# output_controller_schematic.net
KiCad netlist of a schematic drawn in EAGLE
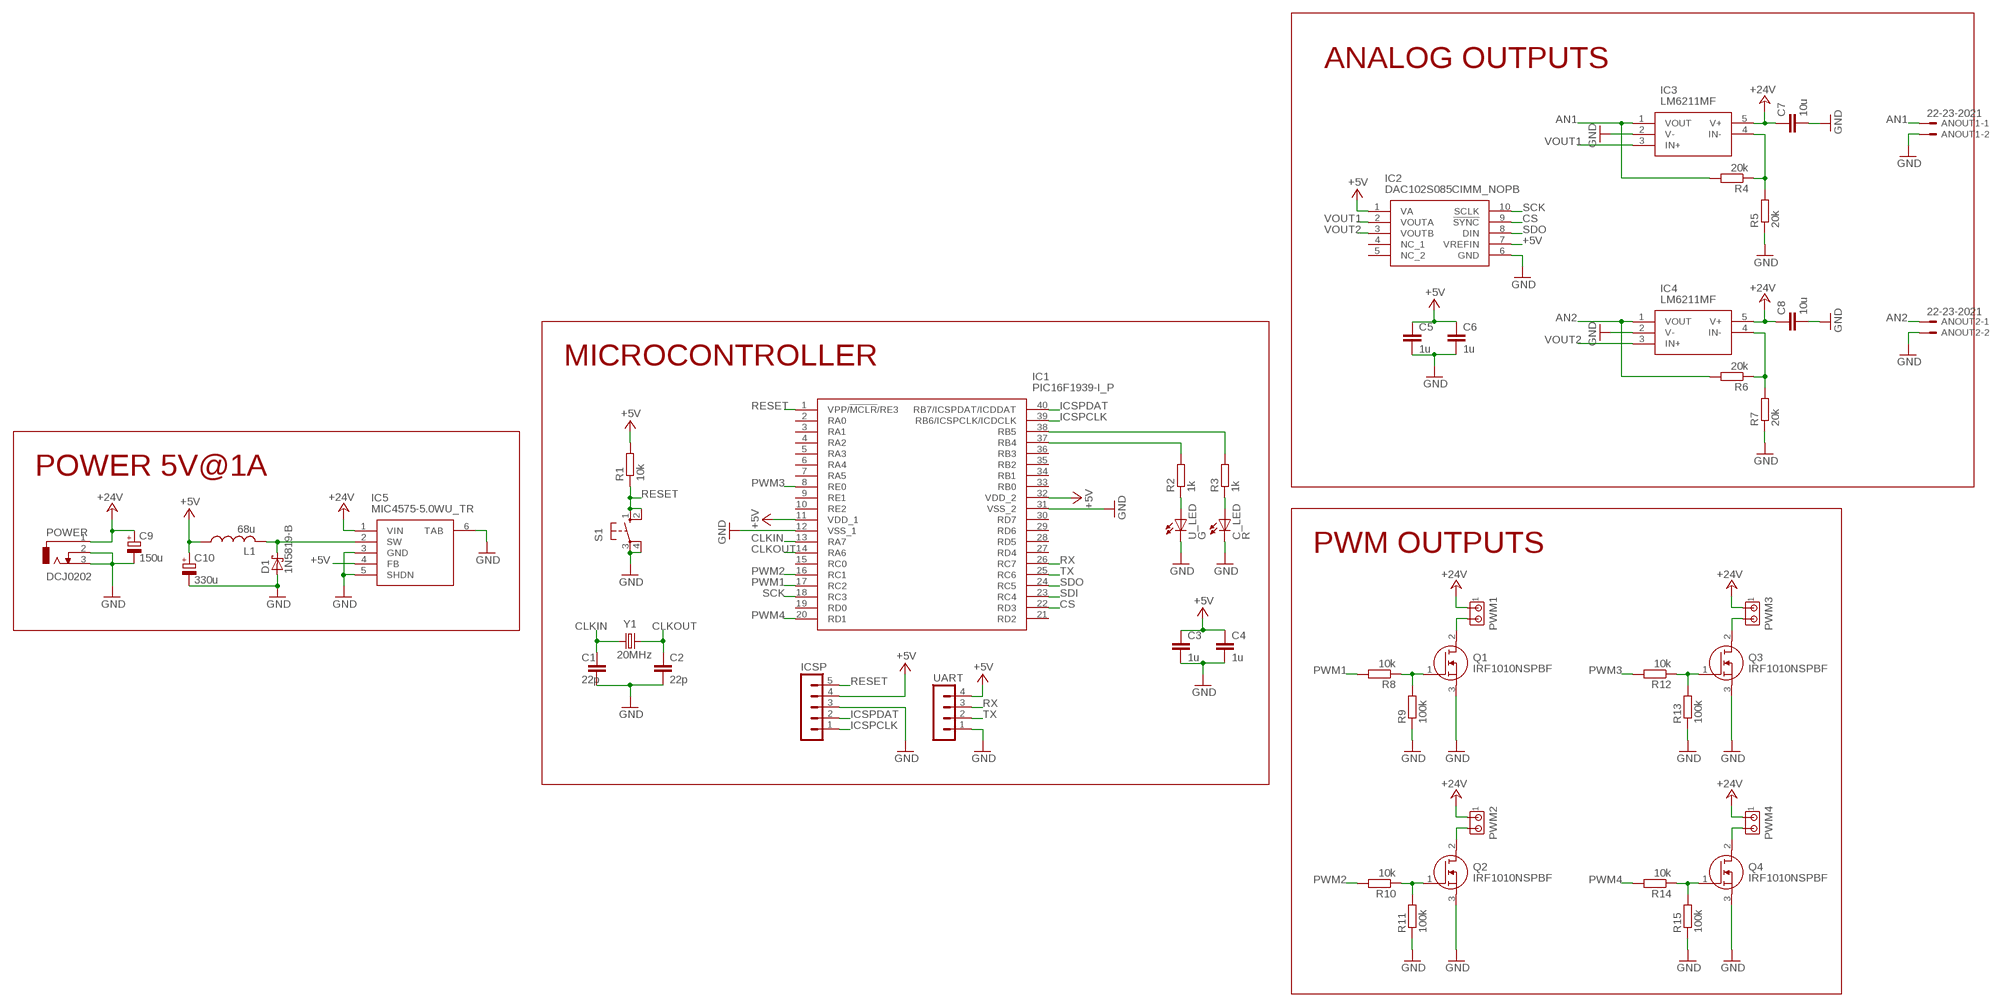
[diagram p0: schematic, sheet 1]

(export (version "E")
  (design (tool "Eeschema 10.0.6"))
  (components
    (comp (ref "ANOUT1")
      (value "22-23-2021")
      (footprint "eagle-import:22-23-2021")
      (fields (field (name "MF") "MOLEX"))
      (libsource (lib "eagle-import") (part "22-23-2021"))
    )
    (comp (ref "ANOUT2")
      (value "22-23-2021")
      (footprint "eagle-import:22-23-2021")
      (fields (field (name "MF") "MOLEX"))
      (libsource (lib "eagle-import") (part "22-23-2021"))
    )
    (comp (ref "C1")
      (value "22p")
      (footprint "eagle-import:C1206")
      (libsource (lib "eagle-import") (part "C-EUC1206"))
    )
    (comp (ref "C2")
      (value "22p")
      (footprint "eagle-import:C1206")
      (libsource (lib "eagle-import") (part "C-EUC1206"))
    )
    (comp (ref "C3")
      (value "1u")
      (footprint "eagle-import:C1206")
      (libsource (lib "eagle-import") (part "C-EUC1206"))
    )
    (comp (ref "C4")
      (value "1u")
      (footprint "eagle-import:C1206")
      (libsource (lib "eagle-import") (part "C-EUC1206"))
    )
    (comp (ref "C5")
      (value "1u")
      (footprint "eagle-import:C1206")
      (libsource (lib "eagle-import") (part "C-EUC1206"))
    )
    (comp (ref "C6")
      (value "1u")
      (footprint "eagle-import:C1206")
      (libsource (lib "eagle-import") (part "C-EUC1206"))
    )
    (comp (ref "C7")
      (value "10u")
      (footprint "eagle-import:C1206")
      (libsource (lib "eagle-import") (part "C-EUC1206"))
    )
    (comp (ref "C8")
      (value "10u")
      (footprint "eagle-import:C1206")
      (libsource (lib "eagle-import") (part "C-EUC1206"))
    )
    (comp (ref "C9")
      (value "150u")
      (footprint "eagle-import:175TMP-0810")
      (libsource (lib "eagle-import") (part "CPOL-EU175TMP-0810"))
    )
    (comp (ref "C10")
      (value "330u")
      (footprint "eagle-import:175TMP-0810")
      (libsource (lib "eagle-import") (part "CPOL-EU175TMP-0810"))
    )
    (comp (ref "C_LED")
      (value "R")
      (footprint "eagle-import:CHIPLED_1206")
      (libsource (lib "eagle-import") (part "LEDCHIPLED_1206"))
    )
    (comp (ref "D1")
      (value "1N5819-B")
      (footprint "eagle-import:DO41-7.6")
      (libsource (lib "eagle-import") (part "1N5819-B"))
    )
    (comp (ref "IC1")
      (value "PIC16F1939-I_P")
      (footprint "eagle-import:DIP1543W58P254L5175H635Q40N")
      (fields
        (field (name "ARROW_PART_NUMBER") "PIC16F1939-I/P")
        (field (name "MOUSER_PART_NUMBER") "579-PIC16F1939-I/P")
      )
      (libsource (lib "eagle-import") (part "PIC16F1939-I_P"))
    )
    (comp (ref "IC2")
      (value "DAC102S085CIMM_NOPB")
      (footprint "eagle-import:SOP50P490X110-10N")
      (fields
        (field (name "ARROW_PART_NUMBER") "DAC102S085CIMM/NOPB")
        (field (name "MOUSER_PART_NUMBER") "926-DA102S085CIMMNPB")
      )
      (libsource (lib "eagle-import") (part "DAC102S085CIMM_NOPB"))
    )
    (comp (ref "IC3")
      (value "LM6211MF")
      (footprint "eagle-import:SOT95P284X122-5N")
      (fields (field (name "MOUSER_PART_NUMBER") "926-LM6211MF"))
      (libsource (lib "eagle-import") (part "LM6211MF"))
    )
    (comp (ref "IC4")
      (value "LM6211MF")
      (footprint "eagle-import:SOT95P284X122-5N")
      (fields (field (name "MOUSER_PART_NUMBER") "926-LM6211MF"))
      (libsource (lib "eagle-import") (part "LM6211MF"))
    )
    (comp (ref "IC5")
      (value "MIC4575-5.0WU_TR")
      (footprint "eagle-import:MIC2930112WU")
      (fields (field (name "ARROW_PART_NUMBER") "MIC4575-5.0WU TR"))
      (libsource (lib "eagle-import") (part "MIC4575-5.0WU_TR"))
    )
    (comp (ref "ICSP")
      (value "MA05-1")
      (footprint "eagle-import:MA05-1")
      (libsource (lib "eagle-import") (part "MA05-1"))
    )
    (comp (ref "L1")
      (value "68u")
      (footprint "eagle-import:L5650M")
      (libsource (lib "eagle-import") (part "L-USL5650M"))
    )
    (comp (ref "POWER")
      (value "DCJ0202")
      (footprint "eagle-import:DCJ0202")
      (libsource (lib "eagle-import") (part "DCJ0202"))
    )
    (comp (ref "PWM1")
      (value "MTA02-156")
      (footprint "eagle-import:1X2MTA")
      (libsource (lib "eagle-import") (part "MTA02-156"))
    )
    (comp (ref "PWM2")
      (value "MTA02-156")
      (footprint "eagle-import:1X2MTA")
      (libsource (lib "eagle-import") (part "MTA02-156"))
    )
    (comp (ref "PWM3")
      (value "MTA02-156")
      (footprint "eagle-import:1X2MTA")
      (libsource (lib "eagle-import") (part "MTA02-156"))
    )
    (comp (ref "PWM4")
      (value "MTA02-156")
      (footprint "eagle-import:1X2MTA")
      (libsource (lib "eagle-import") (part "MTA02-156"))
    )
    (comp (ref "Q1")
      (value "IRF1010NSPBF")
      (footprint "eagle-import:IRF2804STRLPBF")
      (fields (field (name "MOUSER_PART_NUMBER") "942-IRF1010NSPBF"))
      (libsource (lib "eagle-import") (part "IRF1010NSPBF"))
    )
    (comp (ref "Q2")
      (value "IRF1010NSPBF")
      (footprint "eagle-import:IRF2804STRLPBF")
      (fields (field (name "MOUSER_PART_NUMBER") "942-IRF1010NSPBF"))
      (libsource (lib "eagle-import") (part "IRF1010NSPBF"))
    )
    (comp (ref "Q3")
      (value "IRF1010NSPBF")
      (footprint "eagle-import:IRF2804STRLPBF")
      (fields (field (name "MOUSER_PART_NUMBER") "942-IRF1010NSPBF"))
      (libsource (lib "eagle-import") (part "IRF1010NSPBF"))
    )
    (comp (ref "Q4")
      (value "IRF1010NSPBF")
      (footprint "eagle-import:IRF2804STRLPBF")
      (fields (field (name "MOUSER_PART_NUMBER") "942-IRF1010NSPBF"))
      (libsource (lib "eagle-import") (part "IRF1010NSPBF"))
    )
    (comp (ref "R1")
      (value "10k")
      (footprint "eagle-import:R1206")
      (libsource (lib "eagle-import") (part "R-EU_R1206"))
    )
    (comp (ref "R2")
      (value "1k")
      (footprint "eagle-import:R1206")
      (libsource (lib "eagle-import") (part "R-EU_R1206"))
    )
    (comp (ref "R3")
      (value "1k")
      (footprint "eagle-import:R1206")
      (libsource (lib "eagle-import") (part "R-EU_R1206"))
    )
    (comp (ref "R4")
      (value "20k")
      (footprint "eagle-import:R1206")
      (libsource (lib "eagle-import") (part "R-EU_R1206"))
    )
    (comp (ref "R5")
      (value "20k")
      (footprint "eagle-import:R1206")
      (libsource (lib "eagle-import") (part "R-EU_R1206"))
    )
    (comp (ref "R6")
      (value "20k")
      (footprint "eagle-import:R1206")
      (libsource (lib "eagle-import") (part "R-EU_R1206"))
    )
    (comp (ref "R7")
      (value "20k")
      (footprint "eagle-import:R1206")
      (libsource (lib "eagle-import") (part "R-EU_R1206"))
    )
    (comp (ref "R8")
      (value "10k")
      (footprint "eagle-import:R1206")
      (libsource (lib "eagle-import") (part "R-EU_R1206"))
    )
    (comp (ref "R9")
      (value "100k")
      (footprint "eagle-import:R1206")
      (libsource (lib "eagle-import") (part "R-EU_R1206"))
    )
    (comp (ref "R10")
      (value "10k")
      (footprint "eagle-import:R1206")
      (libsource (lib "eagle-import") (part "R-EU_R1206"))
    )
    (comp (ref "R11")
      (value "100k")
      (footprint "eagle-import:R1206")
      (libsource (lib "eagle-import") (part "R-EU_R1206"))
    )
    (comp (ref "R12")
      (value "10k")
      (footprint "eagle-import:R1206")
      (libsource (lib "eagle-import") (part "R-EU_R1206"))
    )
    (comp (ref "R13")
      (value "100k")
      (footprint "eagle-import:R1206")
      (libsource (lib "eagle-import") (part "R-EU_R1206"))
    )
    (comp (ref "R14")
      (value "10k")
      (footprint "eagle-import:R1206")
      (libsource (lib "eagle-import") (part "R-EU_R1206"))
    )
    (comp (ref "R15")
      (value "100k")
      (footprint "eagle-import:R1206")
      (libsource (lib "eagle-import") (part "R-EU_R1206"))
    )
    (comp (ref "S1")
      (value "10-XX")
      (footprint "eagle-import:B3F-10XX")
      (fields (field (name "MPN") "B3F-1000"))
      (libsource (lib "eagle-import") (part "10-XX"))
    )
    (comp (ref "UART")
      (value "MA04-1")
      (footprint "eagle-import:MA04-1")
      (libsource (lib "eagle-import") (part "MA04-1"))
    )
    (comp (ref "U_LED")
      (value "G")
      (footprint "eagle-import:CHIPLED_1206")
      (libsource (lib "eagle-import") (part "LEDCHIPLED_1206"))
    )
    (comp (ref "Y1")
      (value "20MHz")
      (footprint "eagle-import:HC49_S")
      (libsource (lib "eagle-import") (part "CRYSTALHC49S"))
    )
  )
  (nets
    (net (code "1") (name "+5V") (class "Default")
      (node (ref "C10") (pin "+") (pinfunction "+_+") (pintype "passive"))
      (node (ref "C3") (pin "1") (pinfunction "1_1") (pintype "passive"))
      (node (ref "C4") (pin "1") (pinfunction "1_1") (pintype "passive"))
      (node (ref "C5") (pin "1") (pinfunction "1_1") (pintype "passive"))
      (node (ref "C6") (pin "1") (pinfunction "1_1") (pintype "passive"))
      (node (ref "IC1") (pin "11") (pinfunction "VDD_1_11") (pintype "bidirectional"))
      (node (ref "IC1") (pin "32") (pinfunction "VDD_2_32") (pintype "bidirectional"))
      (node (ref "IC2") (pin "1") (pinfunction "VA_1") (pintype "bidirectional"))
      (node (ref "IC2") (pin "7") (pinfunction "VREFIN_7") (pintype "bidirectional"))
      (node (ref "IC5") (pin "4") (pinfunction "FB_4") (pintype "bidirectional"))
      (node (ref "ICSP") (pin "4") (pinfunction "4_4") (pintype "passive"))
      (node (ref "L1") (pin "1") (pinfunction "1_1") (pintype "passive"))
      (node (ref "R1") (pin "2") (pinfunction "2_2") (pintype "passive"))
      (node (ref "UART") (pin "4") (pinfunction "4_4") (pintype "passive"))
    )
    (net (code "2") (name "+24V") (class "Default")
      (node (ref "C7") (pin "1") (pinfunction "1_1") (pintype "passive"))
      (node (ref "C8") (pin "1") (pinfunction "1_1") (pintype "passive"))
      (node (ref "C9") (pin "+") (pinfunction "+_+") (pintype "passive"))
      (node (ref "IC3") (pin "5") (pinfunction "V+_5") (pintype "bidirectional"))
      (node (ref "IC4") (pin "5") (pinfunction "V+_5") (pintype "bidirectional"))
      (node (ref "IC5") (pin "1") (pinfunction "VIN_1") (pintype "bidirectional"))
      (node (ref "POWER") (pin "1") (pinfunction "1_1") (pintype "passive"))
      (node (ref "PWM1") (pin "1") (pinfunction "1_1") (pintype "passive"))
      (node (ref "PWM2") (pin "1") (pinfunction "1_1") (pintype "passive"))
      (node (ref "PWM3") (pin "1") (pinfunction "1_1") (pintype "passive"))
      (node (ref "PWM4") (pin "1") (pinfunction "1_1") (pintype "passive"))
    )
    (net (code "3") (name "/AN1") (class "Default")
      (node (ref "ANOUT1") (pin "1") (pinfunction "S_1") (pintype "passive"))
      (node (ref "IC3") (pin "1") (pinfunction "VOUT_1") (pintype "bidirectional"))
      (node (ref "R4") (pin "2") (pinfunction "2_2") (pintype "passive"))
    )
    (net (code "4") (name "/AN2") (class "Default")
      (node (ref "ANOUT2") (pin "1") (pinfunction "S_1") (pintype "passive"))
      (node (ref "IC4") (pin "1") (pinfunction "VOUT_1") (pintype "bidirectional"))
      (node (ref "R6") (pin "2") (pinfunction "2_2") (pintype "passive"))
    )
    (net (code "5") (name "/CLKIN") (class "Default")
      (node (ref "C1") (pin "1") (pinfunction "1_1") (pintype "passive"))
      (node (ref "IC1") (pin "13") (pinfunction "RA7_13") (pintype "bidirectional"))
      (node (ref "Y1") (pin "1") (pinfunction "1_1") (pintype "passive"))
    )
    (net (code "6") (name "/CLKOUT") (class "Default")
      (node (ref "C2") (pin "1") (pinfunction "1_1") (pintype "passive"))
      (node (ref "IC1") (pin "14") (pinfunction "RA6_14") (pintype "bidirectional"))
      (node (ref "Y1") (pin "2") (pinfunction "2_2") (pintype "passive"))
    )
    (net (code "7") (name "/CS") (class "Default")
      (node (ref "IC1") (pin "22") (pinfunction "RD3_22") (pintype "bidirectional"))
      (node (ref "IC2") (pin "9") (pinfunction "~{SYNC}_9") (pintype "bidirectional"))
    )
    (net (code "8") (name "/ICSPCLK") (class "Default")
      (node (ref "IC1") (pin "39") (pinfunction "RB6/ICSPCLK/ICDCLK_39") (pintype "bidirectional"))
      (node (ref "ICSP") (pin "1") (pinfunction "1_1") (pintype "passive"))
    )
    (net (code "9") (name "/ICSPDAT") (class "Default")
      (node (ref "IC1") (pin "40") (pinfunction "RB7/ICSPDAT/ICDDAT_40") (pintype "bidirectional"))
      (node (ref "ICSP") (pin "2") (pinfunction "2_2") (pintype "passive"))
    )
    (net (code "10") (name "/PWM1") (class "Default")
      (node (ref "IC1") (pin "17") (pinfunction "RC2_17") (pintype "bidirectional"))
      (node (ref "R8") (pin "2") (pinfunction "2_2") (pintype "passive"))
    )
    (net (code "11") (name "/PWM2") (class "Default")
      (node (ref "IC1") (pin "16") (pinfunction "RC1_16") (pintype "bidirectional"))
      (node (ref "R10") (pin "2") (pinfunction "2_2") (pintype "passive"))
    )
    (net (code "12") (name "/PWM3") (class "Default")
      (node (ref "IC1") (pin "8") (pinfunction "RE0_8") (pintype "bidirectional"))
      (node (ref "R12") (pin "2") (pinfunction "2_2") (pintype "passive"))
    )
    (net (code "13") (name "/PWM4") (class "Default")
      (node (ref "IC1") (pin "20") (pinfunction "RD1_20") (pintype "bidirectional"))
      (node (ref "R14") (pin "2") (pinfunction "2_2") (pintype "passive"))
    )
    (net (code "14") (name "/RESET") (class "Default")
      (node (ref "IC1") (pin "1") (pinfunction "VPP/~{MCLR}/RE3_1") (pintype "bidirectional"))
      (node (ref "ICSP") (pin "5") (pinfunction "5_5") (pintype "passive"))
      (node (ref "R1") (pin "1") (pinfunction "1_1") (pintype "passive"))
      (node (ref "S1") (pin "1") (pinfunction "S_1") (pintype "passive"))
      (node (ref "S1") (pin "2") (pinfunction "S1_2") (pintype "passive"))
    )
    (net (code "15") (name "/RX") (class "Default")
      (node (ref "IC1") (pin "26") (pinfunction "RC7_26") (pintype "bidirectional"))
      (node (ref "UART") (pin "3") (pinfunction "3_3") (pintype "passive"))
    )
    (net (code "16") (name "/SCK") (class "Default")
      (node (ref "IC1") (pin "18") (pinfunction "RC3_18") (pintype "bidirectional"))
      (node (ref "IC2") (pin "10") (pinfunction "SCLK_10") (pintype "bidirectional"))
    )
    (net (code "17") (name "/SDI") (class "Default")
      (node (ref "IC1") (pin "23") (pinfunction "RC4_23") (pintype "bidirectional"))
    )
    (net (code "18") (name "/SDO") (class "Default")
      (node (ref "IC1") (pin "24") (pinfunction "RC5_24") (pintype "bidirectional"))
      (node (ref "IC2") (pin "8") (pinfunction "DIN_8") (pintype "bidirectional"))
    )
    (net (code "19") (name "/TX") (class "Default")
      (node (ref "IC1") (pin "25") (pinfunction "RC6_25") (pintype "bidirectional"))
      (node (ref "UART") (pin "2") (pinfunction "2_2") (pintype "passive"))
    )
    (net (code "20") (name "/VOUT1") (class "Default")
      (node (ref "IC2") (pin "2") (pinfunction "VOUTA_2") (pintype "bidirectional"))
      (node (ref "IC3") (pin "3") (pinfunction "IN+_3") (pintype "bidirectional"))
    )
    (net (code "21") (name "/VOUT2") (class "Default")
      (node (ref "IC2") (pin "3") (pinfunction "VOUTB_3") (pintype "bidirectional"))
      (node (ref "IC4") (pin "3") (pinfunction "IN+_3") (pintype "bidirectional"))
    )
    (net (code "22") (name "GND") (class "Default")
      (node (ref "ANOUT1") (pin "2") (pinfunction "S_2") (pintype "passive"))
      (node (ref "ANOUT2") (pin "2") (pinfunction "S_2") (pintype "passive"))
      (node (ref "C1") (pin "2") (pinfunction "2_2") (pintype "passive"))
      (node (ref "C10") (pin "-") (pinfunction "-_-") (pintype "passive"))
      (node (ref "C2") (pin "2") (pinfunction "2_2") (pintype "passive"))
      (node (ref "C3") (pin "2") (pinfunction "2_2") (pintype "passive"))
      (node (ref "C4") (pin "2") (pinfunction "2_2") (pintype "passive"))
      (node (ref "C5") (pin "2") (pinfunction "2_2") (pintype "passive"))
      (node (ref "C6") (pin "2") (pinfunction "2_2") (pintype "passive"))
      (node (ref "C7") (pin "2") (pinfunction "2_2") (pintype "passive"))
      (node (ref "C8") (pin "2") (pinfunction "2_2") (pintype "passive"))
      (node (ref "C9") (pin "-") (pinfunction "-_-") (pintype "passive"))
      (node (ref "C_LED") (pin "C") (pinfunction "C_C") (pintype "passive"))
      (node (ref "D1") (pin "A") (pinfunction "A_A") (pintype "passive"))
      (node (ref "IC1") (pin "12") (pinfunction "VSS_1_12") (pintype "bidirectional"))
      (node (ref "IC1") (pin "31") (pinfunction "VSS_2_31") (pintype "bidirectional"))
      (node (ref "IC2") (pin "6") (pinfunction "GND_6") (pintype "bidirectional"))
      (node (ref "IC3") (pin "2") (pinfunction "V-_2") (pintype "bidirectional"))
      (node (ref "IC4") (pin "2") (pinfunction "V-_2") (pintype "bidirectional"))
      (node (ref "IC5") (pin "3") (pinfunction "GND_3") (pintype "bidirectional"))
      (node (ref "IC5") (pin "5") (pinfunction "SHDN_5") (pintype "bidirectional"))
      (node (ref "IC5") (pin "6") (pinfunction "TAB_6") (pintype "bidirectional"))
      (node (ref "ICSP") (pin "3") (pinfunction "3_3") (pintype "passive"))
      (node (ref "POWER") (pin "2") (pinfunction "2_2") (pintype "passive"))
      (node (ref "POWER") (pin "3") (pinfunction "3_3") (pintype "passive"))
      (node (ref "Q1") (pin "3") (pinfunction "S_3") (pintype "bidirectional"))
      (node (ref "Q2") (pin "3") (pinfunction "S_3") (pintype "bidirectional"))
      (node (ref "Q3") (pin "3") (pinfunction "S_3") (pintype "bidirectional"))
      (node (ref "Q4") (pin "3") (pinfunction "S_3") (pintype "bidirectional"))
      (node (ref "R11") (pin "1") (pinfunction "1_1") (pintype "passive"))
      (node (ref "R13") (pin "1") (pinfunction "1_1") (pintype "passive"))
      (node (ref "R15") (pin "1") (pinfunction "1_1") (pintype "passive"))
      (node (ref "R5") (pin "1") (pinfunction "1_1") (pintype "passive"))
      (node (ref "R7") (pin "1") (pinfunction "1_1") (pintype "passive"))
      (node (ref "R9") (pin "1") (pinfunction "1_1") (pintype "passive"))
      (node (ref "S1") (pin "3") (pinfunction "P_3") (pintype "passive"))
      (node (ref "S1") (pin "4") (pinfunction "P1_4") (pintype "passive"))
      (node (ref "UART") (pin "1") (pinfunction "1_1") (pintype "passive"))
      (node (ref "U_LED") (pin "C") (pinfunction "C_C") (pintype "passive"))
    )
    (net (code "23") (name "Net-(C_LED-PadA)") (class "Default")
      (node (ref "C_LED") (pin "A") (pinfunction "A_A") (pintype "passive"))
      (node (ref "R3") (pin "1") (pinfunction "1_1") (pintype "passive"))
    )
    (net (code "24") (name "Net-(IC1-RB4)") (class "Default")
      (node (ref "IC1") (pin "37") (pinfunction "RB4_37") (pintype "bidirectional"))
      (node (ref "R2") (pin "2") (pinfunction "2_2") (pintype "passive"))
    )
    (net (code "25") (name "Net-(IC1-RB5)") (class "Default")
      (node (ref "IC1") (pin "38") (pinfunction "RB5_38") (pintype "bidirectional"))
      (node (ref "R3") (pin "2") (pinfunction "2_2") (pintype "passive"))
    )
    (net (code "26") (name "Net-(IC3-IN-)") (class "Default")
      (node (ref "IC3") (pin "4") (pinfunction "IN-_4") (pintype "bidirectional"))
      (node (ref "R4") (pin "1") (pinfunction "1_1") (pintype "passive"))
      (node (ref "R5") (pin "2") (pinfunction "2_2") (pintype "passive"))
    )
    (net (code "27") (name "Net-(IC4-IN-)") (class "Default")
      (node (ref "IC4") (pin "4") (pinfunction "IN-_4") (pintype "bidirectional"))
      (node (ref "R6") (pin "1") (pinfunction "1_1") (pintype "passive"))
      (node (ref "R7") (pin "2") (pinfunction "2_2") (pintype "passive"))
    )
    (net (code "28") (name "Net-(IC5-SW)") (class "Default")
      (node (ref "D1") (pin "C") (pinfunction "C_C") (pintype "passive"))
      (node (ref "IC5") (pin "2") (pinfunction "SW_2") (pintype "bidirectional"))
      (node (ref "L1") (pin "2") (pinfunction "2_2") (pintype "passive"))
    )
    (net (code "29") (name "Net-(Q1-D)") (class "Default")
      (node (ref "PWM1") (pin "2") (pinfunction "2_2") (pintype "passive"))
      (node (ref "Q1") (pin "2") (pinfunction "D_2") (pintype "bidirectional"))
    )
    (net (code "30") (name "Net-(Q1-G)") (class "Default")
      (node (ref "Q1") (pin "1") (pinfunction "G_1") (pintype "bidirectional"))
      (node (ref "R8") (pin "1") (pinfunction "1_1") (pintype "passive"))
      (node (ref "R9") (pin "2") (pinfunction "2_2") (pintype "passive"))
    )
    (net (code "31") (name "Net-(Q2-D)") (class "Default")
      (node (ref "PWM2") (pin "2") (pinfunction "2_2") (pintype "passive"))
      (node (ref "Q2") (pin "2") (pinfunction "D_2") (pintype "bidirectional"))
    )
    (net (code "32") (name "Net-(Q2-G)") (class "Default")
      (node (ref "Q2") (pin "1") (pinfunction "G_1") (pintype "bidirectional"))
      (node (ref "R10") (pin "1") (pinfunction "1_1") (pintype "passive"))
      (node (ref "R11") (pin "2") (pinfunction "2_2") (pintype "passive"))
    )
    (net (code "33") (name "Net-(Q3-D)") (class "Default")
      (node (ref "PWM3") (pin "2") (pinfunction "2_2") (pintype "passive"))
      (node (ref "Q3") (pin "2") (pinfunction "D_2") (pintype "bidirectional"))
    )
    (net (code "34") (name "Net-(Q3-G)") (class "Default")
      (node (ref "Q3") (pin "1") (pinfunction "G_1") (pintype "bidirectional"))
      (node (ref "R12") (pin "1") (pinfunction "1_1") (pintype "passive"))
      (node (ref "R13") (pin "2") (pinfunction "2_2") (pintype "passive"))
    )
    (net (code "35") (name "Net-(Q4-D)") (class "Default")
      (node (ref "PWM4") (pin "2") (pinfunction "2_2") (pintype "passive"))
      (node (ref "Q4") (pin "2") (pinfunction "D_2") (pintype "bidirectional"))
    )
    (net (code "36") (name "Net-(Q4-G)") (class "Default")
      (node (ref "Q4") (pin "1") (pinfunction "G_1") (pintype "bidirectional"))
      (node (ref "R14") (pin "1") (pinfunction "1_1") (pintype "passive"))
      (node (ref "R15") (pin "2") (pinfunction "2_2") (pintype "passive"))
    )
    (net (code "37") (name "Net-(R2-Pad1)") (class "Default")
      (node (ref "R2") (pin "1") (pinfunction "1_1") (pintype "passive"))
      (node (ref "U_LED") (pin "A") (pinfunction "A_A") (pintype "passive"))
    )
    (net (code "38") (name "unconnected-(IC1-RA0-Pad2)") (class "Default")
      (node (ref "IC1") (pin "2") (pinfunction "RA0_2") (pintype "bidirectional"))
    )
    (net (code "39") (name "unconnected-(IC1-RA1-Pad3)") (class "Default")
      (node (ref "IC1") (pin "3") (pinfunction "RA1_3") (pintype "bidirectional"))
    )
    (net (code "40") (name "unconnected-(IC1-RA2-Pad4)") (class "Default")
      (node (ref "IC1") (pin "4") (pinfunction "RA2_4") (pintype "bidirectional"))
    )
    (net (code "41") (name "unconnected-(IC1-RA3-Pad5)") (class "Default")
      (node (ref "IC1") (pin "5") (pinfunction "RA3_5") (pintype "bidirectional"))
    )
    (net (code "42") (name "unconnected-(IC1-RA4-Pad6)") (class "Default")
      (node (ref "IC1") (pin "6") (pinfunction "RA4_6") (pintype "bidirectional"))
    )
    (net (code "43") (name "unconnected-(IC1-RA5-Pad7)") (class "Default")
      (node (ref "IC1") (pin "7") (pinfunction "RA5_7") (pintype "bidirectional"))
    )
    (net (code "44") (name "unconnected-(IC1-RB0-Pad33)") (class "Default")
      (node (ref "IC1") (pin "33") (pinfunction "RB0_33") (pintype "bidirectional"))
    )
    (net (code "45") (name "unconnected-(IC1-RB1-Pad34)") (class "Default")
      (node (ref "IC1") (pin "34") (pinfunction "RB1_34") (pintype "bidirectional"))
    )
    (net (code "46") (name "unconnected-(IC1-RB2-Pad35)") (class "Default")
      (node (ref "IC1") (pin "35") (pinfunction "RB2_35") (pintype "bidirectional"))
    )
    (net (code "47") (name "unconnected-(IC1-RB3-Pad36)") (class "Default")
      (node (ref "IC1") (pin "36") (pinfunction "RB3_36") (pintype "bidirectional"))
    )
    (net (code "48") (name "unconnected-(IC1-RC0-Pad15)") (class "Default")
      (node (ref "IC1") (pin "15") (pinfunction "RC0_15") (pintype "bidirectional"))
    )
    (net (code "49") (name "unconnected-(IC1-RD0-Pad19)") (class "Default")
      (node (ref "IC1") (pin "19") (pinfunction "RD0_19") (pintype "bidirectional"))
    )
    (net (code "50") (name "unconnected-(IC1-RD2-Pad21)") (class "Default")
      (node (ref "IC1") (pin "21") (pinfunction "RD2_21") (pintype "bidirectional"))
    )
    (net (code "51") (name "unconnected-(IC1-RD4-Pad27)") (class "Default")
      (node (ref "IC1") (pin "27") (pinfunction "RD4_27") (pintype "bidirectional"))
    )
    (net (code "52") (name "unconnected-(IC1-RD5-Pad28)") (class "Default")
      (node (ref "IC1") (pin "28") (pinfunction "RD5_28") (pintype "bidirectional"))
    )
    (net (code "53") (name "unconnected-(IC1-RD6-Pad29)") (class "Default")
      (node (ref "IC1") (pin "29") (pinfunction "RD6_29") (pintype "bidirectional"))
    )
    (net (code "54") (name "unconnected-(IC1-RD7-Pad30)") (class "Default")
      (node (ref "IC1") (pin "30") (pinfunction "RD7_30") (pintype "bidirectional"))
    )
    (net (code "55") (name "unconnected-(IC1-RE1-Pad9)") (class "Default")
      (node (ref "IC1") (pin "9") (pinfunction "RE1_9") (pintype "bidirectional"))
    )
    (net (code "56") (name "unconnected-(IC1-RE2-Pad10)") (class "Default")
      (node (ref "IC1") (pin "10") (pinfunction "RE2_10") (pintype "bidirectional"))
    )
    (net (code "57") (name "unconnected-(IC2-NC_1-Pad4)") (class "Default")
      (node (ref "IC2") (pin "4") (pinfunction "NC_1_4") (pintype "bidirectional"))
    )
    (net (code "58") (name "unconnected-(IC2-NC_2-Pad5)") (class "Default")
      (node (ref "IC2") (pin "5") (pinfunction "NC_2_5") (pintype "bidirectional"))
    )
  )
)
